# Ring_1.net
KiCad netlist of a schematic drawn in Altium Designer
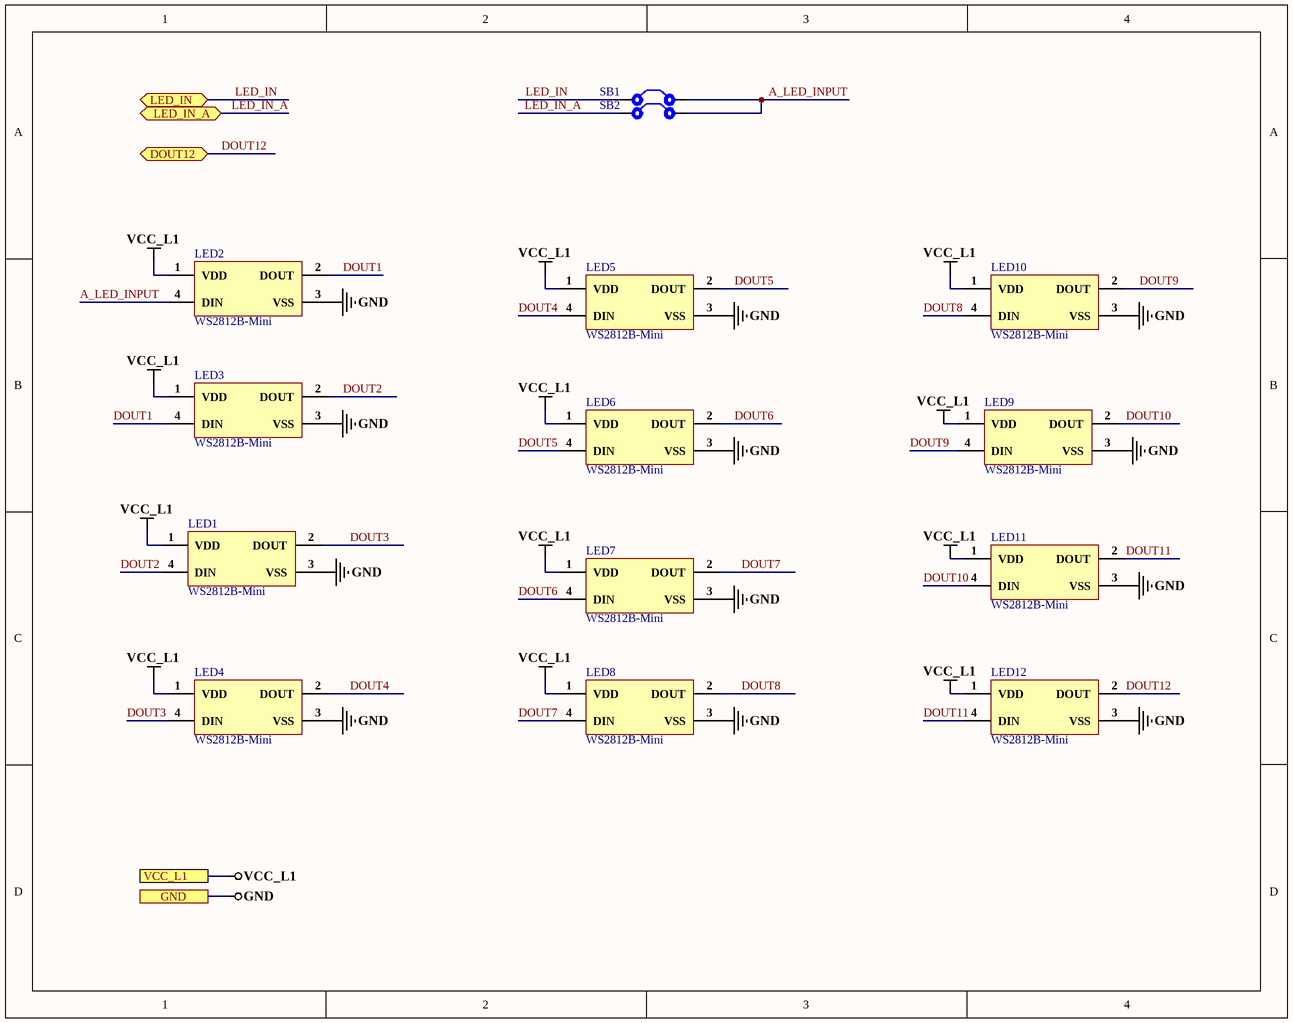
[diagram p0: Ring 1.SchDoc]

(export (version "E")
  (design (tool "Eeschema 10.0.6"))
  (components
    (comp (ref "LED1")
      (value "WS2812B-Mini")
      (footprint "WS2812B-Mini")
      (description "SMD,3.5x3.5mm Light Emitting Diodes (LED) RoHS")
      (fields (field (name "MANUFACTURER") "Worldsemi"))
      (libsource (lib "TT_IntLib") (part "WS2812B-Mini"))
    )
    (comp (ref "LED2")
      (value "WS2812B-Mini")
      (footprint "WS2812B-Mini")
      (description "SMD,3.5x3.5mm Light Emitting Diodes (LED) RoHS")
      (fields (field (name "MANUFACTURER") "Worldsemi"))
      (libsource (lib "TT_IntLib") (part "WS2812B-Mini"))
    )
    (comp (ref "LED3")
      (value "WS2812B-Mini")
      (footprint "WS2812B-Mini")
      (description "SMD,3.5x3.5mm Light Emitting Diodes (LED) RoHS")
      (fields (field (name "MANUFACTURER") "Worldsemi"))
      (libsource (lib "TT_IntLib") (part "WS2812B-Mini"))
    )
    (comp (ref "LED4")
      (value "WS2812B-Mini")
      (footprint "WS2812B-Mini")
      (description "SMD,3.5x3.5mm Light Emitting Diodes (LED) RoHS")
      (fields (field (name "MANUFACTURER") "Worldsemi"))
      (libsource (lib "TT_IntLib") (part "WS2812B-Mini"))
    )
    (comp (ref "LED5")
      (value "WS2812B-Mini")
      (footprint "WS2812B-Mini")
      (description "SMD,3.5x3.5mm Light Emitting Diodes (LED) RoHS")
      (fields (field (name "MANUFACTURER") "Worldsemi"))
      (libsource (lib "TT_IntLib") (part "WS2812B-Mini"))
    )
    (comp (ref "LED6")
      (value "WS2812B-Mini")
      (footprint "WS2812B-Mini")
      (description "SMD,3.5x3.5mm Light Emitting Diodes (LED) RoHS")
      (fields (field (name "MANUFACTURER") "Worldsemi"))
      (libsource (lib "TT_IntLib") (part "WS2812B-Mini"))
    )
    (comp (ref "LED7")
      (value "WS2812B-Mini")
      (footprint "WS2812B-Mini")
      (description "SMD,3.5x3.5mm Light Emitting Diodes (LED) RoHS")
      (fields (field (name "MANUFACTURER") "Worldsemi"))
      (libsource (lib "TT_IntLib") (part "WS2812B-Mini"))
    )
    (comp (ref "LED8")
      (value "WS2812B-Mini")
      (footprint "WS2812B-Mini")
      (description "SMD,3.5x3.5mm Light Emitting Diodes (LED) RoHS")
      (fields (field (name "MANUFACTURER") "Worldsemi"))
      (libsource (lib "TT_IntLib") (part "WS2812B-Mini"))
    )
    (comp (ref "LED9")
      (value "WS2812B-Mini")
      (footprint "WS2812B-Mini")
      (description "SMD,3.5x3.5mm Light Emitting Diodes (LED) RoHS")
      (fields (field (name "MANUFACTURER") "Worldsemi"))
      (libsource (lib "TT_IntLib") (part "WS2812B-Mini"))
    )
    (comp (ref "LED10")
      (value "WS2812B-Mini")
      (footprint "WS2812B-Mini")
      (description "SMD,3.5x3.5mm Light Emitting Diodes (LED) RoHS")
      (fields (field (name "MANUFACTURER") "Worldsemi"))
      (libsource (lib "TT_IntLib") (part "WS2812B-Mini"))
    )
    (comp (ref "LED11")
      (value "WS2812B-Mini")
      (footprint "WS2812B-Mini")
      (description "SMD,3.5x3.5mm Light Emitting Diodes (LED) RoHS")
      (fields (field (name "MANUFACTURER") "Worldsemi"))
      (libsource (lib "TT_IntLib") (part "WS2812B-Mini"))
    )
    (comp (ref "LED12")
      (value "WS2812B-Mini")
      (footprint "WS2812B-Mini")
      (description "SMD,3.5x3.5mm Light Emitting Diodes (LED) RoHS")
      (fields (field (name "MANUFACTURER") "Worldsemi"))
      (libsource (lib "TT_IntLib") (part "WS2812B-Mini"))
    )
    (comp (ref "SB1")
      (value "Solder Bridge")
      (footprint "Solder Bridge")
      (description "Solder Bridge ON")
      (libsource (lib "TT_IntLib") (part "Solder Bridge"))
    )
    (comp (ref "SB2")
      (value "Solder Bridge")
      (footprint "Solder Bridge")
      (description "Solder Bridge ON")
      (libsource (lib "TT_IntLib") (part "Solder Bridge"))
    )
  )
  (nets
    (net (code "1") (name "/A_LED_INPUT") (class "Default")
      (node (ref "LED2") (pin "4") (pinfunction "DIN_4") (pintype "passive"))
      (node (ref "SB1") (pin "2") (pinfunction "2_2") (pintype "passive"))
      (node (ref "SB2") (pin "2") (pinfunction "2_2") (pintype "passive"))
    )
    (net (code "2") (name "/DOUT1") (class "Default")
      (node (ref "LED2") (pin "2") (pinfunction "DOUT_2") (pintype "passive"))
      (node (ref "LED3") (pin "4") (pinfunction "DIN_4") (pintype "passive"))
    )
    (net (code "3") (name "/DOUT2") (class "Default")
      (node (ref "LED1") (pin "4") (pinfunction "DIN_4") (pintype "passive"))
      (node (ref "LED3") (pin "2") (pinfunction "DOUT_2") (pintype "passive"))
    )
    (net (code "4") (name "/DOUT3") (class "Default")
      (node (ref "LED1") (pin "2") (pinfunction "DOUT_2") (pintype "passive"))
      (node (ref "LED4") (pin "4") (pinfunction "DIN_4") (pintype "passive"))
    )
    (net (code "5") (name "/DOUT4") (class "Default")
      (node (ref "LED4") (pin "2") (pinfunction "DOUT_2") (pintype "passive"))
      (node (ref "LED5") (pin "4") (pinfunction "DIN_4") (pintype "passive"))
    )
    (net (code "6") (name "/DOUT5") (class "Default")
      (node (ref "LED5") (pin "2") (pinfunction "DOUT_2") (pintype "passive"))
      (node (ref "LED6") (pin "4") (pinfunction "DIN_4") (pintype "passive"))
    )
    (net (code "7") (name "/DOUT6") (class "Default")
      (node (ref "LED6") (pin "2") (pinfunction "DOUT_2") (pintype "passive"))
      (node (ref "LED7") (pin "4") (pinfunction "DIN_4") (pintype "passive"))
    )
    (net (code "8") (name "/DOUT7") (class "Default")
      (node (ref "LED7") (pin "2") (pinfunction "DOUT_2") (pintype "passive"))
      (node (ref "LED8") (pin "4") (pinfunction "DIN_4") (pintype "passive"))
    )
    (net (code "9") (name "/DOUT8") (class "Default")
      (node (ref "LED10") (pin "4") (pinfunction "DIN_4") (pintype "passive"))
      (node (ref "LED8") (pin "2") (pinfunction "DOUT_2") (pintype "passive"))
    )
    (net (code "10") (name "/DOUT9") (class "Default")
      (node (ref "LED10") (pin "2") (pinfunction "DOUT_2") (pintype "passive"))
      (node (ref "LED9") (pin "4") (pinfunction "DIN_4") (pintype "passive"))
    )
    (net (code "11") (name "/DOUT10") (class "Default")
      (node (ref "LED11") (pin "4") (pinfunction "DIN_4") (pintype "passive"))
      (node (ref "LED9") (pin "2") (pinfunction "DOUT_2") (pintype "passive"))
    )
    (net (code "12") (name "/DOUT11") (class "Default")
      (node (ref "LED11") (pin "2") (pinfunction "DOUT_2") (pintype "passive"))
      (node (ref "LED12") (pin "4") (pinfunction "DIN_4") (pintype "passive"))
    )
    (net (code "13") (name "/DOUT12") (class "Default")
      (node (ref "LED12") (pin "2") (pinfunction "DOUT_2") (pintype "passive"))
    )
    (net (code "14") (name "/LED_IN") (class "Default")
      (node (ref "SB1") (pin "1") (pinfunction "1_1") (pintype "passive"))
    )
    (net (code "15") (name "/LED_IN_A") (class "Default")
      (node (ref "SB2") (pin "1") (pinfunction "1_1") (pintype "passive"))
    )
    (net (code "16") (name "GND") (class "Default")
      (node (ref "LED1") (pin "3") (pinfunction "VSS_3") (pintype "passive"))
      (node (ref "LED10") (pin "3") (pinfunction "VSS_3") (pintype "passive"))
      (node (ref "LED11") (pin "3") (pinfunction "VSS_3") (pintype "passive"))
      (node (ref "LED12") (pin "3") (pinfunction "VSS_3") (pintype "passive"))
      (node (ref "LED2") (pin "3") (pinfunction "VSS_3") (pintype "passive"))
      (node (ref "LED3") (pin "3") (pinfunction "VSS_3") (pintype "passive"))
      (node (ref "LED4") (pin "3") (pinfunction "VSS_3") (pintype "passive"))
      (node (ref "LED5") (pin "3") (pinfunction "VSS_3") (pintype "passive"))
      (node (ref "LED6") (pin "3") (pinfunction "VSS_3") (pintype "passive"))
      (node (ref "LED7") (pin "3") (pinfunction "VSS_3") (pintype "passive"))
      (node (ref "LED8") (pin "3") (pinfunction "VSS_3") (pintype "passive"))
      (node (ref "LED9") (pin "3") (pinfunction "VSS_3") (pintype "passive"))
    )
    (net (code "17") (name "VCC_L1") (class "Default")
      (node (ref "LED1") (pin "1") (pinfunction "VDD_1") (pintype "passive"))
      (node (ref "LED10") (pin "1") (pinfunction "VDD_1") (pintype "passive"))
      (node (ref "LED11") (pin "1") (pinfunction "VDD_1") (pintype "passive"))
      (node (ref "LED12") (pin "1") (pinfunction "VDD_1") (pintype "passive"))
      (node (ref "LED2") (pin "1") (pinfunction "VDD_1") (pintype "passive"))
      (node (ref "LED3") (pin "1") (pinfunction "VDD_1") (pintype "passive"))
      (node (ref "LED4") (pin "1") (pinfunction "VDD_1") (pintype "passive"))
      (node (ref "LED5") (pin "1") (pinfunction "VDD_1") (pintype "passive"))
      (node (ref "LED6") (pin "1") (pinfunction "VDD_1") (pintype "passive"))
      (node (ref "LED7") (pin "1") (pinfunction "VDD_1") (pintype "passive"))
      (node (ref "LED8") (pin "1") (pinfunction "VDD_1") (pintype "passive"))
      (node (ref "LED9") (pin "1") (pinfunction "VDD_1") (pintype "passive"))
    )
  )
)
